# 4501-WB-AV-BMS-REV-C.net
KiCad netlist of a schematic drawn in Altium Designer
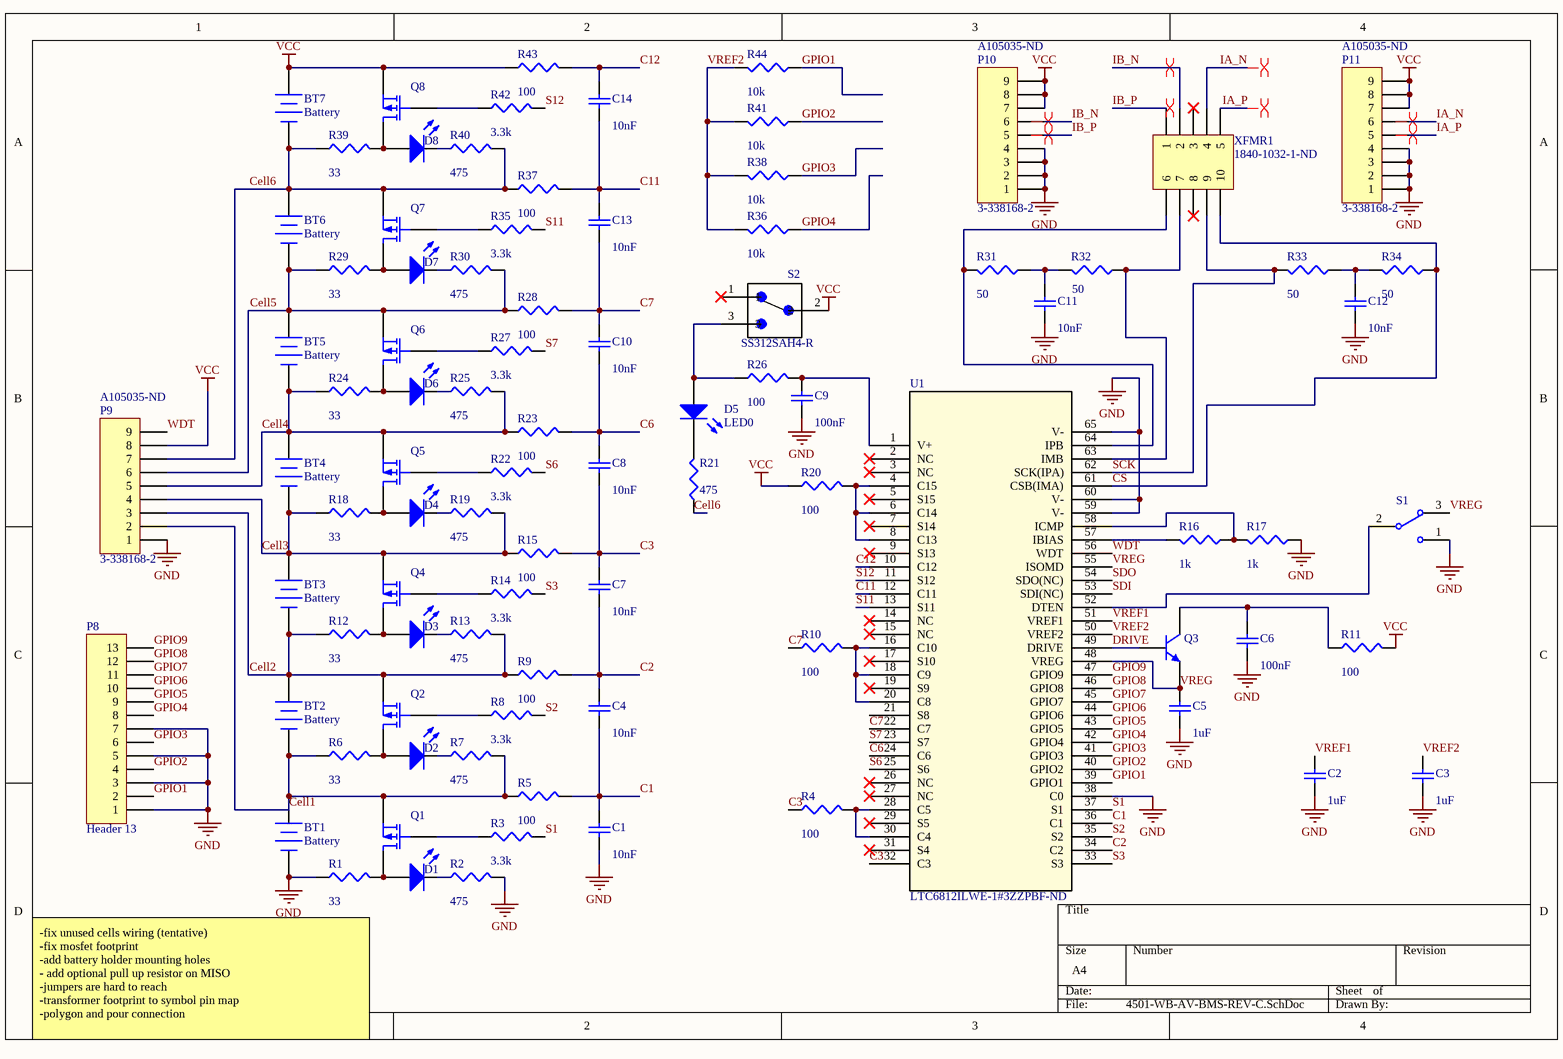
[diagram p0: 4501-WB-AV-BMS-REV-C.SchDoc]

(export (version "E")
  (design (tool "Eeschema 10.0.6"))
  (components
    (comp (ref "BT1")
      (value "Battery")
      (footprint "1043_KEY")
      (description "Multicell Battery")
      (fields (field (name "PUBLISHER") "Altium Limited"))
      (libsource (lib "Miscellaneous Devices") (part "Battery"))
    )
    (comp (ref "BT2")
      (value "Battery")
      (footprint "1043_KEY")
      (description "Multicell Battery")
      (fields (field (name "PUBLISHER") "Altium Limited"))
      (libsource (lib "Miscellaneous Devices") (part "Battery"))
    )
    (comp (ref "BT3")
      (value "Battery")
      (footprint "1043_KEY")
      (description "Multicell Battery")
      (fields (field (name "PUBLISHER") "Altium Limited"))
      (libsource (lib "Miscellaneous Devices") (part "Battery"))
    )
    (comp (ref "BT4")
      (value "Battery")
      (footprint "1043_KEY")
      (description "Multicell Battery")
      (fields (field (name "PUBLISHER") "Altium Limited"))
      (libsource (lib "Miscellaneous Devices") (part "Battery"))
    )
    (comp (ref "BT5")
      (value "Battery")
      (footprint "1043_KEY")
      (description "Multicell Battery")
      (fields (field (name "PUBLISHER") "Altium Limited"))
      (libsource (lib "Miscellaneous Devices") (part "Battery"))
    )
    (comp (ref "BT6")
      (value "Battery")
      (footprint "1043_KEY")
      (description "Multicell Battery")
      (fields (field (name "PUBLISHER") "Altium Limited"))
      (libsource (lib "Miscellaneous Devices") (part "Battery"))
    )
    (comp (ref "BT7")
      (value "Battery")
      (footprint "1043_KEY")
      (description "Multicell Battery")
      (fields (field (name "PUBLISHER") "Altium Limited"))
      (libsource (lib "Miscellaneous Devices") (part "Battery"))
    )
    (comp (ref "C1")
      (value "10nF")
      (footprint "1608[0603]")
      (description "Capacitor (Semiconductor SIM Model)")
      (fields (field (name "Comment") "399-1092-1-ND") (field (name "PUBLISHER") "Altium Limited"))
      (libsource (lib "Miscellaneous Devices") (part "Cap Semi"))
    )
    (comp (ref "C2")
      (value "1uF")
      (footprint "6-0805_N")
      (description "Capacitor (Semiconductor SIM Model)")
      (fields (field (name "Comment") "311-3498-1-ND") (field (name "PUBLISHER") "Altium Limited"))
      (libsource (lib "Miscellaneous Devices") (part "Cap Semi"))
    )
    (comp (ref "C3")
      (value "1uF")
      (footprint "6-0805_N")
      (description "Capacitor (Semiconductor SIM Model)")
      (fields (field (name "Comment") "311-3498-1-ND") (field (name "PUBLISHER") "Altium Limited"))
      (libsource (lib "Miscellaneous Devices") (part "Cap Semi"))
    )
    (comp (ref "C4")
      (value "10nF")
      (footprint "1608[0603]")
      (description "Capacitor (Semiconductor SIM Model)")
      (fields (field (name "Comment") "399-1092-1-ND") (field (name "PUBLISHER") "Altium Limited"))
      (libsource (lib "Miscellaneous Devices") (part "Cap Semi"))
    )
    (comp (ref "C5")
      (value "1uF")
      (footprint "6-0805_N")
      (description "Capacitor (Semiconductor SIM Model)")
      (fields (field (name "Comment") "311-3498-1-ND") (field (name "PUBLISHER") "Altium Limited"))
      (libsource (lib "Miscellaneous Devices") (part "Cap Semi"))
    )
    (comp (ref "C6")
      (value "100nF")
      (footprint "6-0805_N")
      (description "Capacitor (Semiconductor SIM Model)")
      (fields (field (name "Comment") "1276-1090-1-ND") (field (name "PUBLISHER") "Altium Limited"))
      (libsource (lib "Miscellaneous Devices") (part "Cap Semi"))
    )
    (comp (ref "C7")
      (value "10nF")
      (footprint "1608[0603]")
      (description "Capacitor (Semiconductor SIM Model)")
      (fields (field (name "Comment") "399-1092-1-ND") (field (name "PUBLISHER") "Altium Limited"))
      (libsource (lib "Miscellaneous Devices") (part "Cap Semi"))
    )
    (comp (ref "C8")
      (value "10nF")
      (footprint "1608[0603]")
      (description "Capacitor (Semiconductor SIM Model)")
      (fields (field (name "Comment") "399-1092-1-ND") (field (name "PUBLISHER") "Altium Limited"))
      (libsource (lib "Miscellaneous Devices") (part "Cap Semi"))
    )
    (comp (ref "C9")
      (value "100nF")
      (footprint "6-0805_N")
      (description "Capacitor (Semiconductor SIM Model)")
      (fields (field (name "Comment") "1276-1090-1-ND") (field (name "PUBLISHER") "Altium Limited"))
      (libsource (lib "Miscellaneous Devices") (part "Cap Semi"))
    )
    (comp (ref "C10")
      (value "10nF")
      (footprint "1608[0603]")
      (description "Capacitor (Semiconductor SIM Model)")
      (fields (field (name "Comment") "399-1092-1-ND") (field (name "PUBLISHER") "Altium Limited"))
      (libsource (lib "Miscellaneous Devices") (part "Cap Semi"))
    )
    (comp (ref "C11")
      (value "10nF")
      (footprint "1608[0603]")
      (description "Capacitor (Semiconductor SIM Model)")
      (fields (field (name "Comment") "399-1092-1-ND") (field (name "PUBLISHER") "Altium Limited"))
      (libsource (lib "Miscellaneous Devices") (part "Cap Semi"))
    )
    (comp (ref "C12")
      (value "10nF")
      (footprint "1608[0603]")
      (description "Capacitor (Semiconductor SIM Model)")
      (fields (field (name "Comment") "399-1092-1-ND") (field (name "PUBLISHER") "Altium Limited"))
      (libsource (lib "Miscellaneous Devices") (part "Cap Semi"))
    )
    (comp (ref "C13")
      (value "10nF")
      (footprint "1608[0603]")
      (description "Capacitor (Semiconductor SIM Model)")
      (fields (field (name "Comment") "399-1092-1-ND") (field (name "PUBLISHER") "Altium Limited"))
      (libsource (lib "Miscellaneous Devices") (part "Cap Semi"))
    )
    (comp (ref "C14")
      (value "10nF")
      (footprint "1608[0603]")
      (description "Capacitor (Semiconductor SIM Model)")
      (fields (field (name "Comment") "399-1092-1-ND") (field (name "PUBLISHER") "Altium Limited"))
      (libsource (lib "Miscellaneous Devices") (part "Cap Semi"))
    )
    (comp (ref "D1")
      (value "160-1435-1-ND")
      (footprint "J1-0603")
      (description "Typical INFRARED GaAs LED")
      (fields (field (name "PUBLISHER") "Altium Limited"))
      (libsource (lib "Miscellaneous Devices") (part "LED0"))
    )
    (comp (ref "D2")
      (value "160-1435-1-ND")
      (footprint "J1-0603")
      (description "Typical INFRARED GaAs LED")
      (fields (field (name "PUBLISHER") "Altium Limited"))
      (libsource (lib "Miscellaneous Devices") (part "LED0"))
    )
    (comp (ref "D3")
      (value "160-1435-1-ND")
      (footprint "J1-0603")
      (description "Typical INFRARED GaAs LED")
      (fields (field (name "PUBLISHER") "Altium Limited"))
      (libsource (lib "Miscellaneous Devices") (part "LED0"))
    )
    (comp (ref "D4")
      (value "160-1435-1-ND")
      (footprint "J1-0603")
      (description "Typical INFRARED GaAs LED")
      (fields (field (name "PUBLISHER") "Altium Limited"))
      (libsource (lib "Miscellaneous Devices") (part "LED0"))
    )
    (comp (ref "D5")
      (value "LED0")
      (footprint "J1-0603")
      (description "Typical INFRARED GaAs LED")
      (fields (field (name "PUBLISHER") "Altium Limited"))
      (libsource (lib "Miscellaneous Devices") (part "LED0"))
    )
    (comp (ref "D6")
      (value "160-1435-1-ND")
      (footprint "J1-0603")
      (description "Typical INFRARED GaAs LED")
      (fields (field (name "PUBLISHER") "Altium Limited"))
      (libsource (lib "Miscellaneous Devices") (part "LED0"))
    )
    (comp (ref "D7")
      (value "160-1435-1-ND")
      (footprint "J1-0603")
      (description "Typical INFRARED GaAs LED")
      (fields (field (name "PUBLISHER") "Altium Limited"))
      (libsource (lib "Miscellaneous Devices") (part "LED0"))
    )
    (comp (ref "D8")
      (value "160-1435-1-ND")
      (footprint "J1-0603")
      (description "Typical INFRARED GaAs LED")
      (fields (field (name "PUBLISHER") "Altium Limited"))
      (libsource (lib "Miscellaneous Devices") (part "LED0"))
    )
    (comp (ref "P8")
      (value "Header 13")
      (footprint "DIP10")
      (description "Header, 13-Pin")
      (fields (field (name "PUBLISHER") "Altium Limited"))
      (libsource (lib "Miscellaneous Connectors") (part "Header 13"))
    )
    (comp (ref "P9")
      (value "3-338168-2")
      (footprint "CONN_3-338168-2")
      (description "Header, 9-Pin")
      (fields
        (field (name "SUPPLIER PART NUMBER 1") "A105035-ND")
        (field (name "PUBLISHER") "Altium Limited")
      )
      (libsource (lib "Miscellaneous Connectors") (part "Header 9"))
    )
    (comp (ref "P10")
      (value "3-338168-2")
      (footprint "CONN_3-338168-2")
      (description "Header, 9-Pin")
      (fields
        (field (name "SUPPLIER PART NUMBER 1") "A105035-ND")
        (field (name "PUBLISHER") "Altium Limited")
      )
      (libsource (lib "Miscellaneous Connectors") (part "Header 9"))
    )
    (comp (ref "P11")
      (value "3-338168-2")
      (footprint "CONN_3-338168-2")
      (description "Header, 9-Pin")
      (fields
        (field (name "SUPPLIER PART NUMBER 1") "A105035-ND")
        (field (name "PUBLISHER") "Altium Limited")
      )
      (libsource (lib "Miscellaneous Connectors") (part "Header 9"))
    )
    (comp (ref "Q1")
      (value "BSS308PEH6327XTSA1CT-ND")
      (footprint "SOT95P245X110-3N")
      (description "P-Channel MOSFET")
      (fields (field (name "PUBLISHER") "Altium Limited"))
      (libsource (lib "Miscellaneous Devices") (part "MOSFET-P"))
    )
    (comp (ref "Q2")
      (value "BSS308PEH6327XTSA1CT-ND")
      (footprint "SOT95P245X110-3N")
      (description "P-Channel MOSFET")
      (fields (field (name "PUBLISHER") "Altium Limited"))
      (libsource (lib "Miscellaneous Devices") (part "MOSFET-P"))
    )
    (comp (ref "Q3")
      (value "DXT5551P5-13CT-ND")
      (footprint "DXT5551P5-13")
      (description "NPN General Purpose Amplifier")
      (fields (field (name "PUBLISHER") "Altium Limited"))
      (libsource (lib "Miscellaneous Devices") (part "2N3904"))
    )
    (comp (ref "Q4")
      (value "BSS308PEH6327XTSA1CT-ND")
      (footprint "SOT95P245X110-3N")
      (description "P-Channel MOSFET")
      (fields (field (name "PUBLISHER") "Altium Limited"))
      (libsource (lib "Miscellaneous Devices") (part "MOSFET-P"))
    )
    (comp (ref "Q5")
      (value "BSS308PEH6327XTSA1CT-ND")
      (footprint "SOT95P245X110-3N")
      (description "P-Channel MOSFET")
      (fields (field (name "PUBLISHER") "Altium Limited"))
      (libsource (lib "Miscellaneous Devices") (part "MOSFET-P"))
    )
    (comp (ref "Q6")
      (value "BSS308PEH6327XTSA1CT-ND")
      (footprint "SOT95P245X110-3N")
      (description "P-Channel MOSFET")
      (fields (field (name "PUBLISHER") "Altium Limited"))
      (libsource (lib "Miscellaneous Devices") (part "MOSFET-P"))
    )
    (comp (ref "Q7")
      (value "BSS308PEH6327XTSA1CT-ND")
      (footprint "SOT95P245X110-3N")
      (description "P-Channel MOSFET")
      (fields (field (name "PUBLISHER") "Altium Limited"))
      (libsource (lib "Miscellaneous Devices") (part "MOSFET-P"))
    )
    (comp (ref "Q8")
      (value "BSS308PEH6327XTSA1CT-ND")
      (footprint "SOT95P245X110-3N")
      (description "P-Channel MOSFET")
      (fields (field (name "PUBLISHER") "Altium Limited"))
      (libsource (lib "Miscellaneous Devices") (part "MOSFET-P"))
    )
    (comp (ref "R1")
      (value "33")
      (footprint "12Z-2010")
      (description "Resistor")
      (fields (field (name "Comment") "A130642CT-ND") (field (name "PUBLISHER") "Altium Limited"))
      (libsource (lib "Miscellaneous Devices") (part "Res3"))
    )
    (comp (ref "R2")
      (value "475")
      (footprint "J1-0603")
      (description "Resistor")
      (fields (field (name "Comment") "RMCF2010JT33R0CT-ND") (field (name "PUBLISHER") "Altium Limited"))
      (libsource (lib "Miscellaneous Devices") (part "Res3"))
    )
    (comp (ref "R3")
      (value "3.3k")
      (footprint "J1-0603")
      (description "Resistor")
      (fields (field (name "Comment") "A129543CT-ND") (field (name "PUBLISHER") "Altium Limited"))
      (libsource (lib "Miscellaneous Devices") (part "Res3"))
    )
    (comp (ref "R4")
      (value "100")
      (footprint "J1-0603")
      (description "Resistor")
      (fields (field (name "Comment") "A129676CT-ND") (field (name "PUBLISHER") "Altium Limited"))
      (libsource (lib "Miscellaneous Devices") (part "Res3"))
    )
    (comp (ref "R5")
      (value "100")
      (footprint "J1-0603")
      (description "Resistor")
      (fields (field (name "Comment") "A129676CT-ND") (field (name "PUBLISHER") "Altium Limited"))
      (libsource (lib "Miscellaneous Devices") (part "Res3"))
    )
    (comp (ref "R6")
      (value "33")
      (footprint "12Z-2010")
      (description "Resistor")
      (fields (field (name "Comment") "A130642CT-ND") (field (name "PUBLISHER") "Altium Limited"))
      (libsource (lib "Miscellaneous Devices") (part "Res3"))
    )
    (comp (ref "R7")
      (value "475")
      (footprint "J1-0603")
      (description "Resistor")
      (fields (field (name "Comment") "RMCF2010JT33R0CT-ND") (field (name "PUBLISHER") "Altium Limited"))
      (libsource (lib "Miscellaneous Devices") (part "Res3"))
    )
    (comp (ref "R8")
      (value "3.3k")
      (footprint "J1-0603")
      (description "Resistor")
      (fields (field (name "Comment") "A129543CT-ND") (field (name "PUBLISHER") "Altium Limited"))
      (libsource (lib "Miscellaneous Devices") (part "Res3"))
    )
    (comp (ref "R9")
      (value "100")
      (footprint "J1-0603")
      (description "Resistor")
      (fields (field (name "Comment") "A129676CT-ND") (field (name "PUBLISHER") "Altium Limited"))
      (libsource (lib "Miscellaneous Devices") (part "Res3"))
    )
    (comp (ref "R10")
      (value "100")
      (footprint "J1-0603")
      (description "Resistor")
      (fields (field (name "Comment") "A129676CT-ND") (field (name "PUBLISHER") "Altium Limited"))
      (libsource (lib "Miscellaneous Devices") (part "Res3"))
    )
    (comp (ref "R11")
      (value "100")
      (footprint "J1-0603")
      (description "Resistor")
      (fields (field (name "Comment") "A129676CT-ND") (field (name "PUBLISHER") "Altium Limited"))
      (libsource (lib "Miscellaneous Devices") (part "Res3"))
    )
    (comp (ref "R12")
      (value "33")
      (footprint "12Z-2010")
      (description "Resistor")
      (fields (field (name "Comment") "A130642CT-ND") (field (name "PUBLISHER") "Altium Limited"))
      (libsource (lib "Miscellaneous Devices") (part "Res3"))
    )
    (comp (ref "R13")
      (value "475")
      (footprint "J1-0603")
      (description "Resistor")
      (fields (field (name "Comment") "RMCF2010JT33R0CT-ND") (field (name "PUBLISHER") "Altium Limited"))
      (libsource (lib "Miscellaneous Devices") (part "Res3"))
    )
    (comp (ref "R14")
      (value "3.3k")
      (footprint "J1-0603")
      (description "Resistor")
      (fields (field (name "Comment") "A129543CT-ND") (field (name "PUBLISHER") "Altium Limited"))
      (libsource (lib "Miscellaneous Devices") (part "Res3"))
    )
    (comp (ref "R15")
      (value "100")
      (footprint "J1-0603")
      (description "Resistor")
      (fields (field (name "Comment") "A129676CT-ND") (field (name "PUBLISHER") "Altium Limited"))
      (libsource (lib "Miscellaneous Devices") (part "Res3"))
    )
    (comp (ref "R16")
      (value "1k")
      (footprint "J1-0603")
      (description "Resistor")
      (fields (field (name "Comment") "RNCP0603FTD1K00CT-ND") (field (name "PUBLISHER") "Altium Limited"))
      (libsource (lib "Miscellaneous Devices") (part "Res3"))
    )
    (comp (ref "R17")
      (value "1k")
      (footprint "J1-0603")
      (description "Resistor")
      (fields (field (name "Comment") "RNCP0603FTD1K00CT-ND") (field (name "PUBLISHER") "Altium Limited"))
      (libsource (lib "Miscellaneous Devices") (part "Res3"))
    )
    (comp (ref "R18")
      (value "33")
      (footprint "12Z-2010")
      (description "Resistor")
      (fields (field (name "Comment") "A130642CT-ND") (field (name "PUBLISHER") "Altium Limited"))
      (libsource (lib "Miscellaneous Devices") (part "Res3"))
    )
    (comp (ref "R19")
      (value "475")
      (footprint "J1-0603")
      (description "Resistor")
      (fields (field (name "Comment") "RMCF2010JT33R0CT-ND") (field (name "PUBLISHER") "Altium Limited"))
      (libsource (lib "Miscellaneous Devices") (part "Res3"))
    )
    (comp (ref "R20")
      (value "100")
      (footprint "J1-0603")
      (description "Resistor")
      (fields (field (name "Comment") "A129676CT-ND") (field (name "PUBLISHER") "Altium Limited"))
      (libsource (lib "Miscellaneous Devices") (part "Res3"))
    )
    (comp (ref "R21")
      (value "475")
      (footprint "J1-0603")
      (description "Resistor")
      (fields (field (name "Comment") "RMCF2010JT33R0CT-ND") (field (name "PUBLISHER") "Altium Limited"))
      (libsource (lib "Miscellaneous Devices") (part "Res3"))
    )
    (comp (ref "R22")
      (value "3.3k")
      (footprint "J1-0603")
      (description "Resistor")
      (fields (field (name "Comment") "A129543CT-ND") (field (name "PUBLISHER") "Altium Limited"))
      (libsource (lib "Miscellaneous Devices") (part "Res3"))
    )
    (comp (ref "R23")
      (value "100")
      (footprint "J1-0603")
      (description "Resistor")
      (fields (field (name "Comment") "A129676CT-ND") (field (name "PUBLISHER") "Altium Limited"))
      (libsource (lib "Miscellaneous Devices") (part "Res3"))
    )
    (comp (ref "R24")
      (value "33")
      (footprint "12Z-2010")
      (description "Resistor")
      (fields (field (name "Comment") "A130642CT-ND") (field (name "PUBLISHER") "Altium Limited"))
      (libsource (lib "Miscellaneous Devices") (part "Res3"))
    )
    (comp (ref "R25")
      (value "475")
      (footprint "J1-0603")
      (description "Resistor")
      (fields (field (name "Comment") "RMCF2010JT33R0CT-ND") (field (name "PUBLISHER") "Altium Limited"))
      (libsource (lib "Miscellaneous Devices") (part "Res3"))
    )
    (comp (ref "R26")
      (value "100")
      (footprint "J1-0603")
      (description "Resistor")
      (fields (field (name "Comment") "A129676CT-ND") (field (name "PUBLISHER") "Altium Limited"))
      (libsource (lib "Miscellaneous Devices") (part "Res3"))
    )
    (comp (ref "R27")
      (value "3.3k")
      (footprint "J1-0603")
      (description "Resistor")
      (fields (field (name "Comment") "A129543CT-ND") (field (name "PUBLISHER") "Altium Limited"))
      (libsource (lib "Miscellaneous Devices") (part "Res3"))
    )
    (comp (ref "R28")
      (value "100")
      (footprint "J1-0603")
      (description "Resistor")
      (fields (field (name "Comment") "A129676CT-ND") (field (name "PUBLISHER") "Altium Limited"))
      (libsource (lib "Miscellaneous Devices") (part "Res3"))
    )
    (comp (ref "R29")
      (value "33")
      (footprint "12Z-2010")
      (description "Resistor")
      (fields (field (name "Comment") "A130642CT-ND") (field (name "PUBLISHER") "Altium Limited"))
      (libsource (lib "Miscellaneous Devices") (part "Res3"))
    )
    (comp (ref "R30")
      (value "475")
      (footprint "J1-0603")
      (description "Resistor")
      (fields (field (name "Comment") "RMCF2010JT33R0CT-ND") (field (name "PUBLISHER") "Altium Limited"))
      (libsource (lib "Miscellaneous Devices") (part "Res3"))
    )
    (comp (ref "R31")
      (value "50")
      (footprint "J1-0603")
      (description "Resistor")
      (fields (field (name "Comment") "311-2598-1-ND") (field (name "PUBLISHER") "Altium Limited"))
      (libsource (lib "Miscellaneous Devices") (part "Res3"))
    )
    (comp (ref "R32")
      (value "50")
      (footprint "J1-0603")
      (description "Resistor")
      (fields (field (name "Comment") "311-2598-1-ND") (field (name "PUBLISHER") "Altium Limited"))
      (libsource (lib "Miscellaneous Devices") (part "Res3"))
    )
    (comp (ref "R33")
      (value "50")
      (footprint "J1-0603")
      (description "Resistor")
      (fields (field (name "Comment") "311-2598-1-ND") (field (name "PUBLISHER") "Altium Limited"))
      (libsource (lib "Miscellaneous Devices") (part "Res3"))
    )
    (comp (ref "R34")
      (value "50")
      (footprint "J1-0603")
      (description "Resistor")
      (fields (field (name "Comment") "311-2598-1-ND") (field (name "PUBLISHER") "Altium Limited"))
      (libsource (lib "Miscellaneous Devices") (part "Res3"))
    )
    (comp (ref "R35")
      (value "3.3k")
      (footprint "J1-0603")
      (description "Resistor")
      (fields (field (name "Comment") "A129543CT-ND") (field (name "PUBLISHER") "Altium Limited"))
      (libsource (lib "Miscellaneous Devices") (part "Res3"))
    )
    (comp (ref "R36")
      (value "10k")
      (footprint "J1-0603")
      (description "Resistor")
      (fields (field (name "Comment") "RNCP0603FTD10K0CT-ND") (field (name "PUBLISHER") "Altium Limited"))
      (libsource (lib "Miscellaneous Devices") (part "Res3"))
    )
    (comp (ref "R37")
      (value "100")
      (footprint "J1-0603")
      (description "Resistor")
      (fields (field (name "Comment") "A129676CT-ND") (field (name "PUBLISHER") "Altium Limited"))
      (libsource (lib "Miscellaneous Devices") (part "Res3"))
    )
    (comp (ref "R38")
      (value "10k")
      (footprint "J1-0603")
      (description "Resistor")
      (fields (field (name "Comment") "RNCP0603FTD10K0CT-ND") (field (name "PUBLISHER") "Altium Limited"))
      (libsource (lib "Miscellaneous Devices") (part "Res3"))
    )
    (comp (ref "R39")
      (value "33")
      (footprint "12Z-2010")
      (description "Resistor")
      (fields (field (name "Comment") "A130642CT-ND") (field (name "PUBLISHER") "Altium Limited"))
      (libsource (lib "Miscellaneous Devices") (part "Res3"))
    )
    (comp (ref "R40")
      (value "475")
      (footprint "J1-0603")
      (description "Resistor")
      (fields (field (name "Comment") "RMCF2010JT33R0CT-ND") (field (name "PUBLISHER") "Altium Limited"))
      (libsource (lib "Miscellaneous Devices") (part "Res3"))
    )
    (comp (ref "R41")
      (value "10k")
      (footprint "J1-0603")
      (description "Resistor")
      (fields (field (name "Comment") "RNCP0603FTD10K0CT-ND") (field (name "PUBLISHER") "Altium Limited"))
      (libsource (lib "Miscellaneous Devices") (part "Res3"))
    )
    (comp (ref "R42")
      (value "3.3k")
      (footprint "J1-0603")
      (description "Resistor")
      (fields (field (name "Comment") "A129543CT-ND") (field (name "PUBLISHER") "Altium Limited"))
      (libsource (lib "Miscellaneous Devices") (part "Res3"))
    )
    (comp (ref "R43")
      (value "100")
      (footprint "J1-0603")
      (description "Resistor")
      (fields (field (name "Comment") "A129676CT-ND") (field (name "PUBLISHER") "Altium Limited"))
      (libsource (lib "Miscellaneous Devices") (part "Res3"))
    )
    (comp (ref "R44")
      (value "10k")
      (footprint "J1-0603")
      (description "Resistor")
      (fields (field (name "Comment") "RNCP0603FTD10K0CT-ND") (field (name "PUBLISHER") "Altium Limited"))
      (libsource (lib "Miscellaneous Devices") (part "Res3"))
    )
    (comp (ref "S1")
      (value "S9337-ND, SAM8981-ND")
      (footprint "*TSM-103-01-L-SV")
      (description "SPDT Subminiature Toggle Switch, Right Angle Mounting, Vertical Actuation")
      (fields (field (name "PUBLISHER") "Altium Limited"))
      (libsource (lib "Miscellaneous Devices") (part "SW-SPDT"))
    )
    (comp (ref "S2")
      (value "SS312SAH4-R")
      (footprint "*SW_SS312SAH4-R")
      (description "Switch Slide ON None ON SPDT Side Slide 0.1A 28VAC 28VDC 0.4VA 10000Cycles Gull Wing SMD T/R")
      (fields (field (name "MF") "NKK Switches"))
      (libsource (lib "SS312SAH4-R") (part "SS312SAH4-R"))
    )
    (comp (ref "U1")
      (value "LTC6812ILWE-1#3ZZPBF-ND")
      (footprint "LQFP64_LWE_A - duplicate")
      (description "No Description Available")
      (fields (field (name "COPYRIGHT") "Copyright (C) 2018 Accelerated Designs. All rights reserved"))
      (libsource (lib "LTC6812") (part "LTC6812HLWE-1"))
    )
    (comp (ref "XFMR1")
      (value "1840-1032-1-ND")
      (footprint "HM2100NLT")
      (description "Header, 5-Pin, Dual row\r\nHM2100NLT")
      (fields (field (name "PUBLISHER") "Altium Limited"))
      (libsource (lib "Miscellaneous Connectors") (part "Header 5X2A"))
    )
  )
  (nets
    (net (code "1") (name "/C1") (class "Default")
      (node (ref "C1") (pin "2") (pinfunction "2_2") (pintype "passive"))
      (node (ref "C4") (pin "1") (pinfunction "1_1") (pintype "passive"))
      (node (ref "R5") (pin "2") (pinfunction "2_2") (pintype "passive"))
      (node (ref "U1") (pin "36") (pinfunction "C1_36") (pintype "passive"))
    )
    (net (code "2") (name "/C2") (class "Default")
      (node (ref "C4") (pin "2") (pinfunction "2_2") (pintype "passive"))
      (node (ref "C7") (pin "1") (pinfunction "1_1") (pintype "passive"))
      (node (ref "R9") (pin "2") (pinfunction "2_2") (pintype "passive"))
      (node (ref "U1") (pin "34") (pinfunction "C2_34") (pintype "passive"))
    )
    (net (code "3") (name "/C3") (class "Default")
      (node (ref "C7") (pin "2") (pinfunction "2_2") (pintype "passive"))
      (node (ref "C8") (pin "1") (pinfunction "1_1") (pintype "passive"))
      (node (ref "R15") (pin "2") (pinfunction "2_2") (pintype "passive"))
      (node (ref "R4") (pin "1") (pinfunction "1_1") (pintype "passive"))
      (node (ref "U1") (pin "32") (pinfunction "C3_32") (pintype "passive"))
    )
    (net (code "4") (name "/C6") (class "Default")
      (node (ref "C10") (pin "1") (pinfunction "1_1") (pintype "passive"))
      (node (ref "C8") (pin "2") (pinfunction "2_2") (pintype "passive"))
      (node (ref "R23") (pin "2") (pinfunction "2_2") (pintype "passive"))
      (node (ref "U1") (pin "24") (pinfunction "C6_24") (pintype "passive"))
    )
    (net (code "5") (name "/C7") (class "Default")
      (node (ref "C10") (pin "2") (pinfunction "2_2") (pintype "passive"))
      (node (ref "C13") (pin "1") (pinfunction "1_1") (pintype "passive"))
      (node (ref "R10") (pin "1") (pinfunction "1_1") (pintype "passive"))
      (node (ref "R28") (pin "2") (pinfunction "2_2") (pintype "passive"))
      (node (ref "U1") (pin "22") (pinfunction "C7_22") (pintype "passive"))
    )
    (net (code "6") (name "/C11") (class "Default")
      (node (ref "C13") (pin "2") (pinfunction "2_2") (pintype "passive"))
      (node (ref "C14") (pin "1") (pinfunction "1_1") (pintype "passive"))
      (node (ref "R37") (pin "2") (pinfunction "2_2") (pintype "passive"))
      (node (ref "U1") (pin "12") (pinfunction "C11_12") (pintype "passive"))
    )
    (net (code "7") (name "/C12") (class "Default")
      (node (ref "C14") (pin "2") (pinfunction "2_2") (pintype "passive"))
      (node (ref "R43") (pin "2") (pinfunction "2_2") (pintype "passive"))
      (node (ref "U1") (pin "10") (pinfunction "C12_10") (pintype "passive"))
    )
    (net (code "8") (name "/CS") (class "Default")
      (node (ref "R34") (pin "2") (pinfunction "2_2") (pintype "passive"))
      (node (ref "U1") (pin "61") (pinfunction "CSB(IMA)_61") (pintype "passive"))
      (node (ref "XFMR1") (pin "10") (pinfunction "10_10") (pintype "passive"))
    )
    (net (code "9") (name "/Cell1") (class "Default")
      (node (ref "BT1") (pin "1") (pinfunction "+_1") (pintype "passive"))
      (node (ref "BT2") (pin "2") (pinfunction "-_2") (pintype "passive"))
      (node (ref "P9") (pin "2") (pinfunction "2_2") (pintype "passive"))
      (node (ref "Q1") (pin "3") (pinfunction "S_3") (pintype "passive"))
      (node (ref "R5") (pin "1") (pinfunction "1_1") (pintype "passive"))
      (node (ref "R6") (pin "2") (pinfunction "2_2") (pintype "passive"))
      (node (ref "R7") (pin "1") (pinfunction "1_1") (pintype "passive"))
    )
    (net (code "10") (name "/Cell2") (class "Default")
      (node (ref "BT2") (pin "1") (pinfunction "+_1") (pintype "passive"))
      (node (ref "BT3") (pin "2") (pinfunction "-_2") (pintype "passive"))
      (node (ref "P9") (pin "3") (pinfunction "3_3") (pintype "passive"))
      (node (ref "Q2") (pin "3") (pinfunction "S_3") (pintype "passive"))
      (node (ref "R12") (pin "2") (pinfunction "2_2") (pintype "passive"))
      (node (ref "R13") (pin "1") (pinfunction "1_1") (pintype "passive"))
      (node (ref "R9") (pin "1") (pinfunction "1_1") (pintype "passive"))
    )
    (net (code "11") (name "/Cell3") (class "Default")
      (node (ref "BT3") (pin "1") (pinfunction "+_1") (pintype "passive"))
      (node (ref "BT4") (pin "2") (pinfunction "-_2") (pintype "passive"))
      (node (ref "P9") (pin "4") (pinfunction "4_4") (pintype "passive"))
      (node (ref "Q4") (pin "3") (pinfunction "S_3") (pintype "passive"))
      (node (ref "R15") (pin "1") (pinfunction "1_1") (pintype "passive"))
      (node (ref "R18") (pin "2") (pinfunction "2_2") (pintype "passive"))
      (node (ref "R19") (pin "1") (pinfunction "1_1") (pintype "passive"))
    )
    (net (code "12") (name "/Cell4") (class "Default")
      (node (ref "BT4") (pin "1") (pinfunction "+_1") (pintype "passive"))
      (node (ref "BT5") (pin "2") (pinfunction "-_2") (pintype "passive"))
      (node (ref "P9") (pin "5") (pinfunction "5_5") (pintype "passive"))
      (node (ref "Q5") (pin "3") (pinfunction "S_3") (pintype "passive"))
      (node (ref "R23") (pin "1") (pinfunction "1_1") (pintype "passive"))
      (node (ref "R24") (pin "2") (pinfunction "2_2") (pintype "passive"))
      (node (ref "R25") (pin "1") (pinfunction "1_1") (pintype "passive"))
    )
    (net (code "13") (name "/Cell5") (class "Default")
      (node (ref "BT5") (pin "1") (pinfunction "+_1") (pintype "passive"))
      (node (ref "BT6") (pin "2") (pinfunction "-_2") (pintype "passive"))
      (node (ref "P9") (pin "6") (pinfunction "6_6") (pintype "passive"))
      (node (ref "Q6") (pin "3") (pinfunction "S_3") (pintype "passive"))
      (node (ref "R28") (pin "1") (pinfunction "1_1") (pintype "passive"))
      (node (ref "R29") (pin "2") (pinfunction "2_2") (pintype "passive"))
      (node (ref "R30") (pin "1") (pinfunction "1_1") (pintype "passive"))
    )
    (net (code "14") (name "/Cell6") (class "Default")
      (node (ref "BT6") (pin "1") (pinfunction "+_1") (pintype "passive"))
      (node (ref "BT7") (pin "2") (pinfunction "-_2") (pintype "passive"))
      (node (ref "P9") (pin "7") (pinfunction "7_7") (pintype "passive"))
      (node (ref "Q7") (pin "3") (pinfunction "S_3") (pintype "passive"))
      (node (ref "R21") (pin "2") (pinfunction "2_2") (pintype "passive"))
      (node (ref "R37") (pin "1") (pinfunction "1_1") (pintype "passive"))
      (node (ref "R39") (pin "2") (pinfunction "2_2") (pintype "passive"))
      (node (ref "R40") (pin "1") (pinfunction "1_1") (pintype "passive"))
    )
    (net (code "15") (name "/DRIVE") (class "Default")
      (node (ref "Q3") (pin "2") (pinfunction "B_2") (pintype "passive"))
      (node (ref "U1") (pin "49") (pinfunction "DRIVE_49") (pintype "passive"))
    )
    (net (code "16") (name "/GPIO1") (class "Default")
      (node (ref "P8") (pin "2") (pinfunction "2_2") (pintype "passive"))
      (node (ref "R44") (pin "2") (pinfunction "2_2") (pintype "passive"))
      (node (ref "U1") (pin "39") (pinfunction "GPIO1_39") (pintype "passive"))
    )
    (net (code "17") (name "/GPIO2") (class "Default")
      (node (ref "P8") (pin "4") (pinfunction "4_4") (pintype "passive"))
      (node (ref "R41") (pin "2") (pinfunction "2_2") (pintype "passive"))
      (node (ref "U1") (pin "40") (pinfunction "GPIO2_40") (pintype "passive"))
    )
    (net (code "18") (name "/GPIO3") (class "Default")
      (node (ref "P8") (pin "6") (pinfunction "6_6") (pintype "passive"))
      (node (ref "R38") (pin "2") (pinfunction "2_2") (pintype "passive"))
      (node (ref "U1") (pin "41") (pinfunction "GPIO3_41") (pintype "passive"))
    )
    (net (code "19") (name "/GPIO4") (class "Default")
      (node (ref "P8") (pin "8") (pinfunction "8_8") (pintype "passive"))
      (node (ref "R36") (pin "2") (pinfunction "2_2") (pintype "passive"))
      (node (ref "U1") (pin "42") (pinfunction "GPIO4_42") (pintype "passive"))
    )
    (net (code "20") (name "/GPIO5") (class "Default")
      (node (ref "P8") (pin "9") (pinfunction "9_9") (pintype "passive"))
      (node (ref "U1") (pin "43") (pinfunction "GPIO5_43") (pintype "passive"))
    )
    (net (code "21") (name "/GPIO6") (class "Default")
      (node (ref "P8") (pin "10") (pinfunction "10_10") (pintype "passive"))
      (node (ref "U1") (pin "44") (pinfunction "GPIO6_44") (pintype "passive"))
    )
    (net (code "22") (name "/GPIO7") (class "Default")
      (node (ref "P8") (pin "11") (pinfunction "11_11") (pintype "passive"))
      (node (ref "U1") (pin "45") (pinfunction "GPIO7_45") (pintype "passive"))
    )
    (net (code "23") (name "/GPIO8") (class "Default")
      (node (ref "P8") (pin "12") (pinfunction "12_12") (pintype "passive"))
      (node (ref "U1") (pin "46") (pinfunction "GPIO8_46") (pintype "passive"))
    )
    (net (code "24") (name "/GPIO9") (class "Default")
      (node (ref "P8") (pin "13") (pinfunction "13_13") (pintype "passive"))
      (node (ref "U1") (pin "47") (pinfunction "GPIO9_47") (pintype "passive"))
    )
    (net (code "25") (name "/IA_N") (class "Default")
      (node (ref "P11") (pin "6") (pinfunction "6_6") (pintype "passive"))
      (node (ref "XFMR1") (pin "4") (pinfunction "4_4") (pintype "passive"))
    )
    (net (code "26") (name "/IA_P") (class "Default")
      (node (ref "P11") (pin "5") (pinfunction "5_5") (pintype "passive"))
      (node (ref "XFMR1") (pin "5") (pinfunction "5_5") (pintype "passive"))
    )
    (net (code "27") (name "/IB_N") (class "Default")
      (node (ref "P10") (pin "6") (pinfunction "6_6") (pintype "passive"))
      (node (ref "XFMR1") (pin "2") (pinfunction "2_2") (pintype "passive"))
    )
    (net (code "28") (name "/IB_P") (class "Default")
      (node (ref "P10") (pin "5") (pinfunction "5_5") (pintype "passive"))
      (node (ref "XFMR1") (pin "1") (pinfunction "1_1") (pintype "passive"))
    )
    (net (code "29") (name "/S1") (class "Default")
      (node (ref "R3") (pin "2") (pinfunction "2_2") (pintype "passive"))
      (node (ref "U1") (pin "37") (pinfunction "S1_37") (pintype "passive"))
    )
    (net (code "30") (name "/S2") (class "Default")
      (node (ref "R8") (pin "2") (pinfunction "2_2") (pintype "passive"))
      (node (ref "U1") (pin "35") (pinfunction "S2_35") (pintype "passive"))
    )
    (net (code "31") (name "/S3") (class "Default")
      (node (ref "R14") (pin "2") (pinfunction "2_2") (pintype "passive"))
      (node (ref "U1") (pin "33") (pinfunction "S3_33") (pintype "passive"))
    )
    (net (code "32") (name "/S6") (class "Default")
      (node (ref "R22") (pin "2") (pinfunction "2_2") (pintype "passive"))
      (node (ref "U1") (pin "25") (pinfunction "S6_25") (pintype "passive"))
    )
    (net (code "33") (name "/S7") (class "Default")
      (node (ref "R27") (pin "2") (pinfunction "2_2") (pintype "passive"))
      (node (ref "U1") (pin "23") (pinfunction "S7_23") (pintype "passive"))
    )
    (net (code "34") (name "/S11") (class "Default")
      (node (ref "R35") (pin "2") (pinfunction "2_2") (pintype "passive"))
      (node (ref "U1") (pin "13") (pinfunction "S11_13") (pintype "passive"))
    )
    (net (code "35") (name "/S12") (class "Default")
      (node (ref "R42") (pin "2") (pinfunction "2_2") (pintype "passive"))
      (node (ref "U1") (pin "11") (pinfunction "S12_11") (pintype "passive"))
    )
    (net (code "36") (name "/SCK") (class "Default")
      (node (ref "R33") (pin "1") (pinfunction "1_1") (pintype "passive"))
      (node (ref "U1") (pin "62") (pinfunction "SCK(IPA)_62") (pintype "passive"))
      (node (ref "XFMR1") (pin "9") (pinfunction "9_9") (pintype "passive"))
    )
    (net (code "37") (name "/SDI") (class "Default")
      (node (ref "U1") (pin "53") (pinfunction "SDI(NC)_53") (pintype "passive"))
    )
    (net (code "38") (name "/SDO") (class "Default")
      (node (ref "U1") (pin "54") (pinfunction "SDO(NC)_54") (pintype "passive"))
    )
    (net (code "39") (name "/VREF1") (class "Default")
      (node (ref "C2") (pin "2") (pinfunction "2_2") (pintype "passive"))
      (node (ref "U1") (pin "51") (pinfunction "VREF1_51") (pintype "passive"))
    )
    (net (code "40") (name "/VREF2") (class "Default")
      (node (ref "C3") (pin "2") (pinfunction "2_2") (pintype "passive"))
      (node (ref "R36") (pin "1") (pinfunction "1_1") (pintype "passive"))
      (node (ref "R38") (pin "1") (pinfunction "1_1") (pintype "passive"))
      (node (ref "R41") (pin "1") (pinfunction "1_1") (pintype "passive"))
      (node (ref "R44") (pin "1") (pinfunction "1_1") (pintype "passive"))
      (node (ref "U1") (pin "50") (pinfunction "VREF2_50") (pintype "passive"))
    )
    (net (code "41") (name "/VREG") (class "Default")
      (node (ref "C5") (pin "2") (pinfunction "2_2") (pintype "passive"))
      (node (ref "Q3") (pin "1") (pinfunction "E_1") (pintype "passive"))
      (node (ref "S1") (pin "3") (pinfunction "3_3") (pintype "passive"))
      (node (ref "U1") (pin "48") (pinfunction "VREG_48") (pintype "passive"))
      (node (ref "U1") (pin "55") (pinfunction "ISOMD_55") (pintype "passive"))
    )
    (net (code "42") (name "/WDT") (class "Default")
      (node (ref "P9") (pin "9") (pinfunction "9_9") (pintype "passive"))
      (node (ref "U1") (pin "56") (pinfunction "WDT_56") (pintype "passive"))
    )
    (net (code "43") (name "GND") (class "Default")
      (node (ref "BT1") (pin "2") (pinfunction "-_2") (pintype "passive"))
      (node (ref "C1") (pin "1") (pinfunction "1_1") (pintype "passive"))
      (node (ref "C11") (pin "1") (pinfunction "1_1") (pintype "passive"))
      (node (ref "C12") (pin "1") (pinfunction "1_1") (pintype "passive"))
      (node (ref "C2") (pin "1") (pinfunction "1_1") (pintype "passive"))
      (node (ref "C3") (pin "1") (pinfunction "1_1") (pintype "passive"))
      (node (ref "C5") (pin "1") (pinfunction "1_1") (pintype "passive"))
      (node (ref "C6") (pin "1") (pinfunction "1_1") (pintype "passive"))
      (node (ref "C9") (pin "1") (pinfunction "1_1") (pintype "passive"))
      (node (ref "P10") (pin "1") (pinfunction "1_1") (pintype "passive"))
      (node (ref "P10") (pin "2") (pinfunction "2_2") (pintype "passive"))
      (node (ref "P10") (pin "3") (pinfunction "3_3") (pintype "passive"))
      (node (ref "P10") (pin "4") (pinfunction "4_4") (pintype "passive"))
      (node (ref "P11") (pin "1") (pinfunction "1_1") (pintype "passive"))
      (node (ref "P11") (pin "2") (pinfunction "2_2") (pintype "passive"))
      (node (ref "P11") (pin "3") (pinfunction "3_3") (pintype "passive"))
      (node (ref "P11") (pin "4") (pinfunction "4_4") (pintype "passive"))
      (node (ref "P8") (pin "1") (pinfunction "1_1") (pintype "passive"))
      (node (ref "P8") (pin "3") (pinfunction "3_3") (pintype "passive"))
      (node (ref "P8") (pin "5") (pinfunction "5_5") (pintype "passive"))
      (node (ref "P8") (pin "7") (pinfunction "7_7") (pintype "passive"))
      (node (ref "P9") (pin "1") (pinfunction "1_1") (pintype "passive"))
      (node (ref "R1") (pin "2") (pinfunction "2_2") (pintype "passive"))
      (node (ref "R17") (pin "2") (pinfunction "2_2") (pintype "passive"))
      (node (ref "R2") (pin "1") (pinfunction "1_1") (pintype "passive"))
      (node (ref "S1") (pin "1") (pinfunction "1_1") (pintype "passive"))
      (node (ref "U1") (pin "38") (pinfunction "C0_38") (pintype "passive"))
      (node (ref "U1") (pin "59") (pinfunction "V-_59") (pintype "passive"))
      (node (ref "U1") (pin "60") (pinfunction "V-_60") (pintype "passive"))
      (node (ref "U1") (pin "65") (pinfunction "V-_65") (pintype "passive"))
    )
    (net (code "44") (name "Net-(C11-Pad2)") (class "Default")
      (node (ref "C11") (pin "2") (pinfunction "2_2") (pintype "passive"))
      (node (ref "R31") (pin "2") (pinfunction "2_2") (pintype "passive"))
      (node (ref "R32") (pin "1") (pinfunction "1_1") (pintype "passive"))
    )
    (net (code "45") (name "Net-(C12-Pad2)") (class "Default")
      (node (ref "C12") (pin "2") (pinfunction "2_2") (pintype "passive"))
      (node (ref "R33") (pin "2") (pinfunction "2_2") (pintype "passive"))
      (node (ref "R34") (pin "1") (pinfunction "1_1") (pintype "passive"))
    )
    (net (code "46") (name "Net-(D1-A)") (class "Default")
      (node (ref "D1") (pin "1") (pinfunction "A_1") (pintype "passive"))
      (node (ref "Q1") (pin "1") (pinfunction "D_1") (pintype "passive"))
      (node (ref "R1") (pin "1") (pinfunction "1_1") (pintype "passive"))
    )
    (net (code "47") (name "Net-(D1-K)") (class "Default")
      (node (ref "D1") (pin "2") (pinfunction "K_2") (pintype "passive"))
      (node (ref "R2") (pin "2") (pinfunction "2_2") (pintype "passive"))
    )
    (net (code "48") (name "Net-(D2-A)") (class "Default")
      (node (ref "D2") (pin "1") (pinfunction "A_1") (pintype "passive"))
      (node (ref "Q2") (pin "1") (pinfunction "D_1") (pintype "passive"))
      (node (ref "R6") (pin "1") (pinfunction "1_1") (pintype "passive"))
    )
    (net (code "49") (name "Net-(D2-K)") (class "Default")
      (node (ref "D2") (pin "2") (pinfunction "K_2") (pintype "passive"))
      (node (ref "R7") (pin "2") (pinfunction "2_2") (pintype "passive"))
    )
    (net (code "50") (name "Net-(D3-A)") (class "Default")
      (node (ref "D3") (pin "1") (pinfunction "A_1") (pintype "passive"))
      (node (ref "Q4") (pin "1") (pinfunction "D_1") (pintype "passive"))
      (node (ref "R12") (pin "1") (pinfunction "1_1") (pintype "passive"))
    )
    (net (code "51") (name "Net-(D3-K)") (class "Default")
      (node (ref "D3") (pin "2") (pinfunction "K_2") (pintype "passive"))
      (node (ref "R13") (pin "2") (pinfunction "2_2") (pintype "passive"))
    )
    (net (code "52") (name "Net-(D4-A)") (class "Default")
      (node (ref "D4") (pin "1") (pinfunction "A_1") (pintype "passive"))
      (node (ref "Q5") (pin "1") (pinfunction "D_1") (pintype "passive"))
      (node (ref "R18") (pin "1") (pinfunction "1_1") (pintype "passive"))
    )
    (net (code "53") (name "Net-(D4-K)") (class "Default")
      (node (ref "D4") (pin "2") (pinfunction "K_2") (pintype "passive"))
      (node (ref "R19") (pin "2") (pinfunction "2_2") (pintype "passive"))
    )
    (net (code "54") (name "Net-(D5-A)") (class "Default")
      (node (ref "D5") (pin "1") (pinfunction "A_1") (pintype "passive"))
      (node (ref "R26") (pin "2") (pinfunction "2_2") (pintype "passive"))
      (node (ref "S2") (pin "3") (pinfunction "3_3") (pintype "passive"))
    )
    (net (code "55") (name "Net-(D5-K)") (class "Default")
      (node (ref "D5") (pin "2") (pinfunction "K_2") (pintype "passive"))
      (node (ref "R21") (pin "1") (pinfunction "1_1") (pintype "passive"))
    )
    (net (code "56") (name "Net-(D6-A)") (class "Default")
      (node (ref "D6") (pin "1") (pinfunction "A_1") (pintype "passive"))
      (node (ref "Q6") (pin "1") (pinfunction "D_1") (pintype "passive"))
      (node (ref "R24") (pin "1") (pinfunction "1_1") (pintype "passive"))
    )
    (net (code "57") (name "Net-(D6-K)") (class "Default")
      (node (ref "D6") (pin "2") (pinfunction "K_2") (pintype "passive"))
      (node (ref "R25") (pin "2") (pinfunction "2_2") (pintype "passive"))
    )
    (net (code "58") (name "Net-(D7-A)") (class "Default")
      (node (ref "D7") (pin "1") (pinfunction "A_1") (pintype "passive"))
      (node (ref "Q7") (pin "1") (pinfunction "D_1") (pintype "passive"))
      (node (ref "R29") (pin "1") (pinfunction "1_1") (pintype "passive"))
    )
    (net (code "59") (name "Net-(D7-K)") (class "Default")
      (node (ref "D7") (pin "2") (pinfunction "K_2") (pintype "passive"))
      (node (ref "R30") (pin "2") (pinfunction "2_2") (pintype "passive"))
    )
    (net (code "60") (name "Net-(D8-A)") (class "Default")
      (node (ref "D8") (pin "1") (pinfunction "A_1") (pintype "passive"))
      (node (ref "Q8") (pin "1") (pinfunction "D_1") (pintype "passive"))
      (node (ref "R39") (pin "1") (pinfunction "1_1") (pintype "passive"))
    )
    (net (code "61") (name "Net-(D8-K)") (class "Default")
      (node (ref "D8") (pin "2") (pinfunction "K_2") (pintype "passive"))
      (node (ref "R40") (pin "2") (pinfunction "2_2") (pintype "passive"))
    )
    (net (code "62") (name "Net-(Q1-G)") (class "Default")
      (node (ref "Q1") (pin "2") (pinfunction "G_2") (pintype "passive"))
      (node (ref "R3") (pin "1") (pinfunction "1_1") (pintype "passive"))
    )
    (net (code "63") (name "Net-(Q2-G)") (class "Default")
      (node (ref "Q2") (pin "2") (pinfunction "G_2") (pintype "passive"))
      (node (ref "R8") (pin "1") (pinfunction "1_1") (pintype "passive"))
    )
    (net (code "64") (name "Net-(Q3-C)") (class "Default")
      (node (ref "C6") (pin "2") (pinfunction "2_2") (pintype "passive"))
      (node (ref "Q3") (pin "3") (pinfunction "C_3") (pintype "passive"))
      (node (ref "R11") (pin "1") (pinfunction "1_1") (pintype "passive"))
    )
    (net (code "65") (name "Net-(Q4-G)") (class "Default")
      (node (ref "Q4") (pin "2") (pinfunction "G_2") (pintype "passive"))
      (node (ref "R14") (pin "1") (pinfunction "1_1") (pintype "passive"))
    )
    (net (code "66") (name "Net-(Q5-G)") (class "Default")
      (node (ref "Q5") (pin "2") (pinfunction "G_2") (pintype "passive"))
      (node (ref "R22") (pin "1") (pinfunction "1_1") (pintype "passive"))
    )
    (net (code "67") (name "Net-(Q6-G)") (class "Default")
      (node (ref "Q6") (pin "2") (pinfunction "G_2") (pintype "passive"))
      (node (ref "R27") (pin "1") (pinfunction "1_1") (pintype "passive"))
    )
    (net (code "68") (name "Net-(Q7-G)") (class "Default")
      (node (ref "Q7") (pin "2") (pinfunction "G_2") (pintype "passive"))
      (node (ref "R35") (pin "1") (pinfunction "1_1") (pintype "passive"))
    )
    (net (code "69") (name "Net-(Q8-G)") (class "Default")
      (node (ref "Q8") (pin "2") (pinfunction "G_2") (pintype "passive"))
      (node (ref "R42") (pin "1") (pinfunction "1_1") (pintype "passive"))
    )
    (net (code "70") (name "Net-(U1-C4)") (class "Default")
      (node (ref "R4") (pin "2") (pinfunction "2_2") (pintype "passive"))
      (node (ref "U1") (pin "28") (pinfunction "C5_28") (pintype "passive"))
      (node (ref "U1") (pin "30") (pinfunction "C4_30") (pintype "passive"))
    )
    (net (code "71") (name "Net-(U1-C10)") (class "Default")
      (node (ref "R10") (pin "2") (pinfunction "2_2") (pintype "passive"))
      (node (ref "U1") (pin "16") (pinfunction "C10_16") (pintype "passive"))
      (node (ref "U1") (pin "18") (pinfunction "C9_18") (pintype "passive"))
      (node (ref "U1") (pin "20") (pinfunction "C8_20") (pintype "passive"))
    )
    (net (code "72") (name "Net-(U1-C13)") (class "Default")
      (node (ref "R20") (pin "2") (pinfunction "2_2") (pintype "passive"))
      (node (ref "U1") (pin "4") (pinfunction "C15_4") (pintype "passive"))
      (node (ref "U1") (pin "6") (pinfunction "C14_6") (pintype "passive"))
      (node (ref "U1") (pin "8") (pinfunction "C13_8") (pintype "passive"))
    )
    (net (code "73") (name "Net-(U1-DTEN)") (class "Default")
      (node (ref "S1") (pin "2") (pinfunction "2_2") (pintype "passive"))
      (node (ref "U1") (pin "52") (pinfunction "DTEN_52") (pintype "passive"))
    )
    (net (code "74") (name "Net-(U1-IBIAS)") (class "Default")
      (node (ref "R16") (pin "1") (pinfunction "1_1") (pintype "passive"))
      (node (ref "U1") (pin "57") (pinfunction "IBIAS_57") (pintype "passive"))
    )
    (net (code "75") (name "Net-(U1-ICMP)") (class "Default")
      (node (ref "R16") (pin "2") (pinfunction "2_2") (pintype "passive"))
      (node (ref "R17") (pin "1") (pinfunction "1_1") (pintype "passive"))
      (node (ref "U1") (pin "58") (pinfunction "ICMP_58") (pintype "passive"))
    )
    (net (code "76") (name "Net-(U1-IMB)") (class "Default")
      (node (ref "R32") (pin "2") (pinfunction "2_2") (pintype "passive"))
      (node (ref "U1") (pin "63") (pinfunction "IMB_63") (pintype "passive"))
      (node (ref "XFMR1") (pin "7") (pinfunction "7_7") (pintype "passive"))
    )
    (net (code "77") (name "Net-(U1-IPB)") (class "Default")
      (node (ref "R31") (pin "1") (pinfunction "1_1") (pintype "passive"))
      (node (ref "U1") (pin "64") (pinfunction "IPB_64") (pintype "passive"))
      (node (ref "XFMR1") (pin "6") (pinfunction "6_6") (pintype "passive"))
    )
    (net (code "78") (name "Net-(U1-V+)") (class "Default")
      (node (ref "C9") (pin "2") (pinfunction "2_2") (pintype "passive"))
      (node (ref "R26") (pin "1") (pinfunction "1_1") (pintype "passive"))
      (node (ref "U1") (pin "1") (pinfunction "V+_1") (pintype "passive"))
    )
    (net (code "79") (name "VCC") (class "Default")
      (node (ref "BT7") (pin "1") (pinfunction "+_1") (pintype "passive"))
      (node (ref "P10") (pin "7") (pinfunction "7_7") (pintype "passive"))
      (node (ref "P10") (pin "8") (pinfunction "8_8") (pintype "passive"))
      (node (ref "P10") (pin "9") (pinfunction "9_9") (pintype "passive"))
      (node (ref "P11") (pin "7") (pinfunction "7_7") (pintype "passive"))
      (node (ref "P11") (pin "8") (pinfunction "8_8") (pintype "passive"))
      (node (ref "P11") (pin "9") (pinfunction "9_9") (pintype "passive"))
      (node (ref "P9") (pin "8") (pinfunction "8_8") (pintype "passive"))
      (node (ref "Q8") (pin "3") (pinfunction "S_3") (pintype "passive"))
      (node (ref "R11") (pin "2") (pinfunction "2_2") (pintype "passive"))
      (node (ref "R20") (pin "1") (pinfunction "1_1") (pintype "passive"))
      (node (ref "R43") (pin "1") (pinfunction "1_1") (pintype "passive"))
      (node (ref "S2") (pin "2") (pinfunction "2_2") (pintype "passive"))
    )
    (net (code "80") (name "unconnected-(S2-Pad1)") (class "Default")
      (node (ref "S2") (pin "1") (pinfunction "1_1") (pintype "passive+no_connect"))
    )
    (net (code "81") (name "unconnected-(U1-NC-Pad2)") (class "Default")
      (node (ref "U1") (pin "2") (pinfunction "NC_2") (pintype "passive+no_connect"))
    )
    (net (code "82") (name "unconnected-(U1-NC-Pad3)") (class "Default")
      (node (ref "U1") (pin "3") (pinfunction "NC_3") (pintype "passive+no_connect"))
    )
    (net (code "83") (name "unconnected-(U1-NC-Pad14)") (class "Default")
      (node (ref "U1") (pin "14") (pinfunction "NC_14") (pintype "passive+no_connect"))
    )
    (net (code "84") (name "unconnected-(U1-NC-Pad15)") (class "Default")
      (node (ref "U1") (pin "15") (pinfunction "NC_15") (pintype "passive+no_connect"))
    )
    (net (code "85") (name "unconnected-(U1-NC-Pad26)") (class "Default")
      (node (ref "U1") (pin "26") (pinfunction "NC_26") (pintype "passive+no_connect"))
    )
    (net (code "86") (name "unconnected-(U1-NC-Pad27)") (class "Default")
      (node (ref "U1") (pin "27") (pinfunction "NC_27") (pintype "passive+no_connect"))
    )
    (net (code "87") (name "unconnected-(U1-S4-Pad31)") (class "Default")
      (node (ref "U1") (pin "31") (pinfunction "S4_31") (pintype "passive+no_connect"))
    )
    (net (code "88") (name "unconnected-(U1-S5-Pad29)") (class "Default")
      (node (ref "U1") (pin "29") (pinfunction "S5_29") (pintype "passive+no_connect"))
    )
    (net (code "89") (name "unconnected-(U1-S8-Pad21)") (class "Default")
      (node (ref "U1") (pin "21") (pinfunction "S8_21") (pintype "passive"))
    )
    (net (code "90") (name "unconnected-(U1-S9-Pad19)") (class "Default")
      (node (ref "U1") (pin "19") (pinfunction "S9_19") (pintype "passive+no_connect"))
    )
    (net (code "91") (name "unconnected-(U1-S10-Pad17)") (class "Default")
      (node (ref "U1") (pin "17") (pinfunction "S10_17") (pintype "passive+no_connect"))
    )
    (net (code "92") (name "unconnected-(U1-S13-Pad9)") (class "Default")
      (node (ref "U1") (pin "9") (pinfunction "S13_9") (pintype "passive+no_connect"))
    )
    (net (code "93") (name "unconnected-(U1-S14-Pad7)") (class "Default")
      (node (ref "U1") (pin "7") (pinfunction "S14_7") (pintype "passive+no_connect"))
    )
    (net (code "94") (name "unconnected-(U1-S15-Pad5)") (class "Default")
      (node (ref "U1") (pin "5") (pinfunction "S15_5") (pintype "passive+no_connect"))
    )
    (net (code "95") (name "unconnected-(XFMR1-Pad3)") (class "Default")
      (node (ref "XFMR1") (pin "3") (pinfunction "3_3") (pintype "passive+no_connect"))
    )
    (net (code "96") (name "unconnected-(XFMR1-Pad8)") (class "Default")
      (node (ref "XFMR1") (pin "8") (pinfunction "8_8") (pintype "passive+no_connect"))
    )
  )
)
